# Driver_Stage.net
KiCad netlist of a schematic drawn in Altium Designer
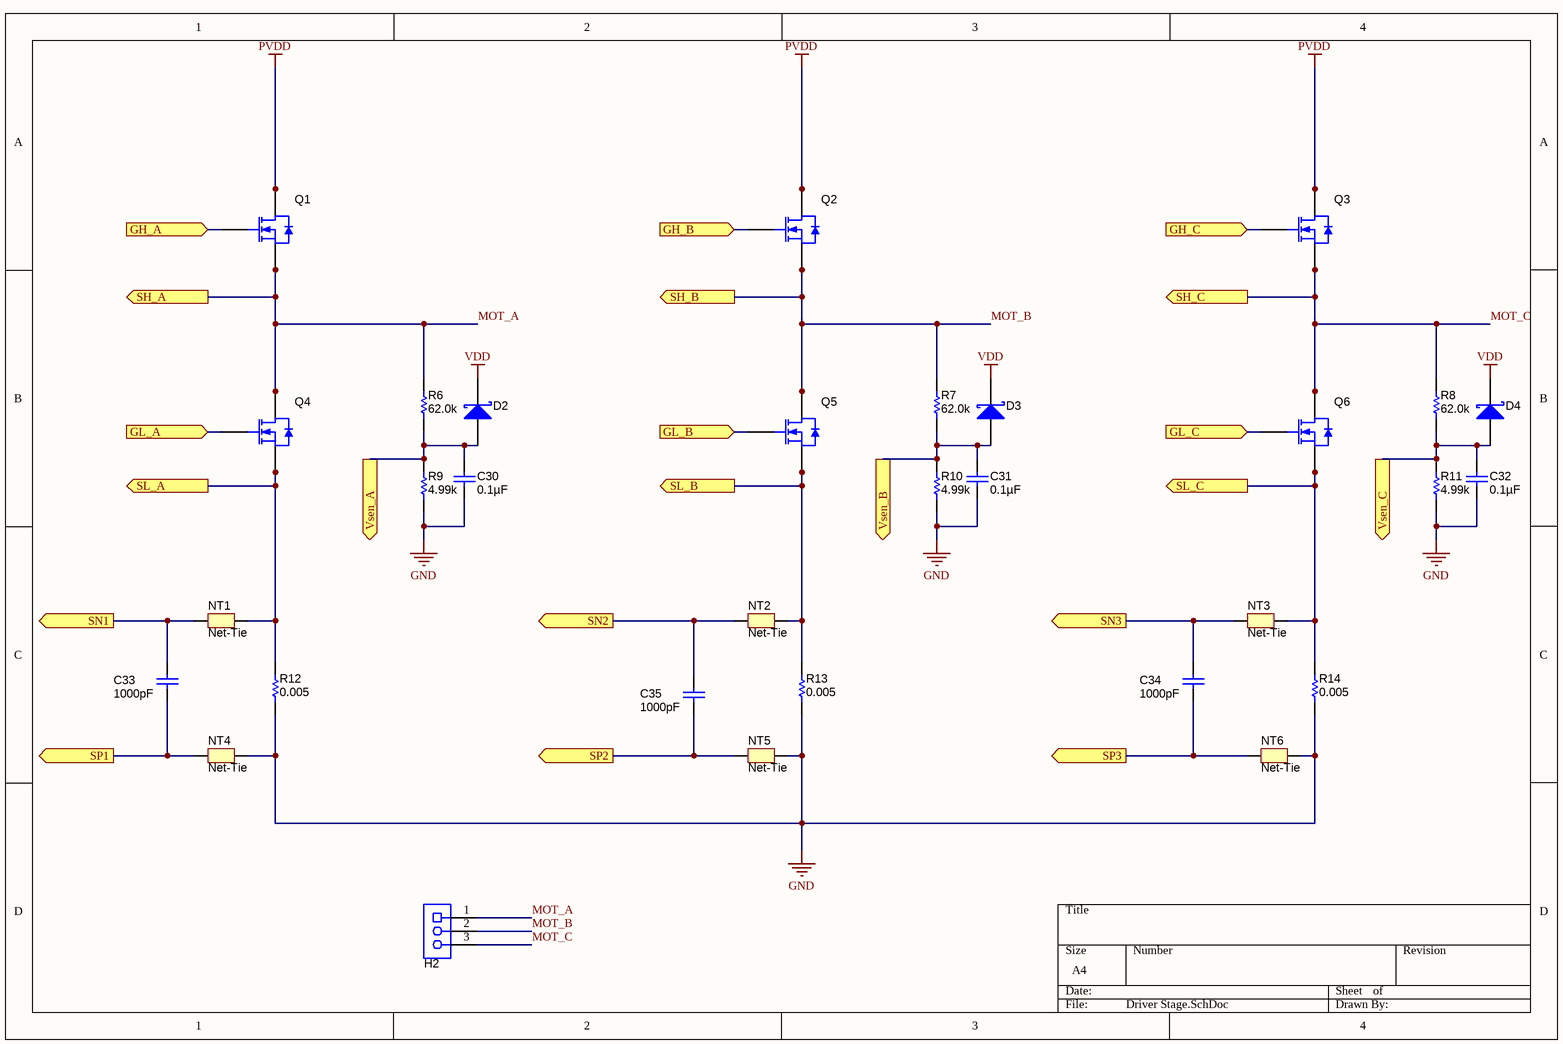
[diagram p0: Driver Stage.SchDoc]

(export (version "E")
  (design (tool "Eeschema 10.0.6"))
  (components
    (comp (ref "C30")
      (value "C0603C104J4RACTU")
      (footprint "MDBU014A:0603L")
      (description "CAP, CERM, 0.1 µF, 16 V, +/- 5%, X7R, 0603")
      (fields
        (field (name "VALUEDISPLAYED") "0.1µF")
        (field (name "MANUFACTURER") "Kemet")
        (field (name "PUBLISHER") "Texas Instruments")
      )
      (libsource (lib "Capacitor_Ceramic") (part "C0603C104J4RACTU"))
    )
    (comp (ref "C31")
      (value "C0603C104J4RACTU")
      (footprint "MDBU014A:0603L")
      (description "CAP, CERM, 0.1 µF, 16 V, +/- 5%, X7R, 0603")
      (fields
        (field (name "VALUEDISPLAYED") "0.1µF")
        (field (name "MANUFACTURER") "Kemet")
        (field (name "PUBLISHER") "Texas Instruments")
      )
      (libsource (lib "Capacitor_Ceramic") (part "C0603C104J4RACTU"))
    )
    (comp (ref "C32")
      (value "C0603C104J4RACTU")
      (footprint "MDBU014A:0603L")
      (description "CAP, CERM, 0.1 µF, 16 V, +/- 5%, X7R, 0603")
      (fields
        (field (name "VALUEDISPLAYED") "0.1µF")
        (field (name "MANUFACTURER") "Kemet")
        (field (name "PUBLISHER") "Texas Instruments")
      )
      (libsource (lib "Capacitor_Ceramic") (part "C0603C104J4RACTU"))
    )
    (comp (ref "C33")
      (value "GRM188R71C102KA01D")
      (footprint "MDBU014A:0603L")
      (description "CAP, CERM, 1000 pF, 16 V, +/- 10%, X7R, 0603")
      (fields
        (field (name "VALUEDISPLAYED") "1000pF")
        (field (name "MANUFACTURER") "MuRata")
        (field (name "PUBLISHER") "Texas Instruments")
      )
      (libsource (lib "Capacitor_Ceramic") (part "GRM188R71C102KA01D"))
    )
    (comp (ref "C34")
      (value "GRM188R71C102KA01D")
      (footprint "MDBU014A:0603L")
      (description "CAP, CERM, 1000 pF, 16 V, +/- 10%, X7R, 0603")
      (fields
        (field (name "VALUEDISPLAYED") "1000pF")
        (field (name "MANUFACTURER") "MuRata")
        (field (name "PUBLISHER") "Texas Instruments")
      )
      (libsource (lib "Capacitor_Ceramic") (part "GRM188R71C102KA01D"))
    )
    (comp (ref "C35")
      (value "GRM188R71C102KA01D")
      (footprint "MDBU014A:0603L")
      (description "CAP, CERM, 1000 pF, 16 V, +/- 10%, X7R, 0603")
      (fields
        (field (name "VALUEDISPLAYED") "1000pF")
        (field (name "MANUFACTURER") "MuRata")
        (field (name "PUBLISHER") "Texas Instruments")
      )
      (libsource (lib "Capacitor_Ceramic") (part "GRM188R71C102KA01D"))
    )
    (comp (ref "D2")
      (value "CD0603-B0130L")
      (footprint "MDBU014A:Diode_0603")
      (description "Diode, Schottky, 35 V, 0.1 A, 0603 Diode")
      (fields (field (name "MANUFACTURER") "Bourns") (field (name "PUBLISHER") "Texas Instruments"))
      (libsource (lib "Diode") (part "CD0603-B0130L"))
    )
    (comp (ref "D3")
      (value "CD0603-B0130L")
      (footprint "MDBU014A:Diode_0603")
      (description "Diode, Schottky, 35 V, 0.1 A, 0603 Diode")
      (fields (field (name "MANUFACTURER") "Bourns") (field (name "PUBLISHER") "Texas Instruments"))
      (libsource (lib "Diode") (part "CD0603-B0130L"))
    )
    (comp (ref "D4")
      (value "CD0603-B0130L")
      (footprint "MDBU014A:Diode_0603")
      (description "Diode, Schottky, 35 V, 0.1 A, 0603 Diode")
      (fields (field (name "MANUFACTURER") "Bourns") (field (name "PUBLISHER") "Texas Instruments"))
      (libsource (lib "Diode") (part "CD0603-B0130L"))
    )
    (comp (ref "H2")
      (value "OSTT7032150")
      (footprint "On-Shore_OSTT7032150")
      (description "Terminal Block, 3x1, 9.52mm, TH")
      (fields
        (field (name "MANUFACTURER") "On-Shore Technology")
        (field (name "SYMBOLCREATOR") "a0412235")
        (field (name "PUBLISHER") "Texas Instruments")
      )
      (libsource (lib "MDBU014A") (part "OSTT7032150"))
    )
    (comp (ref "NT1")
      (value "Net-Tie")
      (footprint "Net-Tie_10mil")
      (description "Single point connection between nets.")
      (fields (field (name "SYMBOLCREATOR") "codlsc") (field (name "PUBLISHER") "Texas Instruments"))
      (libsource (lib "MDBU014A") (part "Net-Tie"))
    )
    (comp (ref "NT2")
      (value "Net-Tie")
      (footprint "Net-Tie_10mil")
      (description "Single point connection between nets.")
      (fields (field (name "SYMBOLCREATOR") "codlsc") (field (name "PUBLISHER") "Texas Instruments"))
      (libsource (lib "MDBU014A") (part "Net-Tie"))
    )
    (comp (ref "NT3")
      (value "Net-Tie")
      (footprint "Net-Tie_10mil")
      (description "Single point connection between nets.")
      (fields (field (name "SYMBOLCREATOR") "codlsc") (field (name "PUBLISHER") "Texas Instruments"))
      (libsource (lib "MDBU014A") (part "Net-Tie"))
    )
    (comp (ref "NT4")
      (value "Net-Tie")
      (footprint "Net-Tie_10mil")
      (description "Single point connection between nets.")
      (fields (field (name "SYMBOLCREATOR") "codlsc") (field (name "PUBLISHER") "Texas Instruments"))
      (libsource (lib "MDBU014A") (part "Net-Tie"))
    )
    (comp (ref "NT5")
      (value "Net-Tie")
      (footprint "Net-Tie_10mil")
      (description "Single point connection between nets.")
      (fields (field (name "SYMBOLCREATOR") "codlsc") (field (name "PUBLISHER") "Texas Instruments"))
      (libsource (lib "MDBU014A") (part "Net-Tie"))
    )
    (comp (ref "NT6")
      (value "Net-Tie")
      (footprint "Net-Tie_10mil")
      (description "Single point connection between nets.")
      (fields (field (name "SYMBOLCREATOR") "codlsc") (field (name "PUBLISHER") "Texas Instruments"))
      (libsource (lib "MDBU014A") (part "Net-Tie"))
    )
    (comp (ref "Q1")
      (value "CSD18540Q5B")
      (footprint "MDBU014A:TRANS_NexFET_Q5B")
      (description "MOSFET, N-CH, 60 V, 28 A, SON 5x6mm")
      (fields
        (field (name "MANUFACTURER") "Texas Instruments")
        (field (name "PUBLISHER") "Texas Instruments")
      )
      (libsource (lib "FETs") (part "CSD18540Q5B"))
    )
    (comp (ref "Q2")
      (value "CSD18540Q5B")
      (footprint "MDBU014A:TRANS_NexFET_Q5B")
      (description "MOSFET, N-CH, 60 V, 28 A, SON 5x6mm")
      (fields
        (field (name "MANUFACTURER") "Texas Instruments")
        (field (name "PUBLISHER") "Texas Instruments")
      )
      (libsource (lib "FETs") (part "CSD18540Q5B"))
    )
    (comp (ref "Q3")
      (value "CSD18540Q5B")
      (footprint "MDBU014A:TRANS_NexFET_Q5B")
      (description "MOSFET, N-CH, 60 V, 28 A, SON 5x6mm")
      (fields
        (field (name "MANUFACTURER") "Texas Instruments")
        (field (name "PUBLISHER") "Texas Instruments")
      )
      (libsource (lib "FETs") (part "CSD18540Q5B"))
    )
    (comp (ref "Q4")
      (value "CSD18540Q5B")
      (footprint "MDBU014A:TRANS_NexFET_Q5B")
      (description "MOSFET, N-CH, 60 V, 28 A, SON 5x6mm")
      (fields
        (field (name "MANUFACTURER") "Texas Instruments")
        (field (name "PUBLISHER") "Texas Instruments")
      )
      (libsource (lib "FETs") (part "CSD18540Q5B"))
    )
    (comp (ref "Q5")
      (value "CSD18540Q5B")
      (footprint "MDBU014A:TRANS_NexFET_Q5B")
      (description "MOSFET, N-CH, 60 V, 28 A, SON 5x6mm")
      (fields
        (field (name "MANUFACTURER") "Texas Instruments")
        (field (name "PUBLISHER") "Texas Instruments")
      )
      (libsource (lib "FETs") (part "CSD18540Q5B"))
    )
    (comp (ref "Q6")
      (value "CSD18540Q5B")
      (footprint "MDBU014A:TRANS_NexFET_Q5B")
      (description "MOSFET, N-CH, 60 V, 28 A, SON 5x6mm")
      (fields
        (field (name "MANUFACTURER") "Texas Instruments")
        (field (name "PUBLISHER") "Texas Instruments")
      )
      (libsource (lib "FETs") (part "CSD18540Q5B"))
    )
    (comp (ref "R6")
      (value "RC0603FR-0762KL")
      (footprint "MDBU014A:0603L")
      (description "RES, 62.0 k, 1%, 0.1 W, 0603")
      (fields
        (field (name "VALUEDISPLAYED") "62.0k")
        (field (name "MANUFACTURER") "Yageo America")
        (field (name "PUBLISHER") "Texas Instruments")
      )
      (libsource (lib "Resistor_0603") (part "RC0603FR-0762KL"))
    )
    (comp (ref "R7")
      (value "RC0603FR-0762KL")
      (footprint "MDBU014A:0603L")
      (description "RES, 62.0 k, 1%, 0.1 W, 0603")
      (fields
        (field (name "VALUEDISPLAYED") "62.0k")
        (field (name "MANUFACTURER") "Yageo America")
        (field (name "PUBLISHER") "Texas Instruments")
      )
      (libsource (lib "Resistor_0603") (part "RC0603FR-0762KL"))
    )
    (comp (ref "R8")
      (value "RC0603FR-0762KL")
      (footprint "MDBU014A:0603L")
      (description "RES, 62.0 k, 1%, 0.1 W, 0603")
      (fields
        (field (name "VALUEDISPLAYED") "62.0k")
        (field (name "MANUFACTURER") "Yageo America")
        (field (name "PUBLISHER") "Texas Instruments")
      )
      (libsource (lib "Resistor_0603") (part "RC0603FR-0762KL"))
    )
    (comp (ref "R9")
      (value "4.99k")
      (footprint "MDBU014A:0603L")
      (description "RES, 4.99 k, 1%, 0.1 W, 0603")
      (fields
        (field (name "PARTNUMBER") "CRCW06034K99FKEA")
        (field (name "MANUFACTURER") "Vishay-Dale")
        (field (name "PUBLISHER") "Texas Instruments")
      )
      (libsource (lib "Resistor_0603") (part "CRCW06034K99FKEA"))
    )
    (comp (ref "R10")
      (value "4.99k")
      (footprint "MDBU014A:0603L")
      (description "RES, 4.99 k, 1%, 0.1 W, 0603")
      (fields
        (field (name "PARTNUMBER") "CRCW06034K99FKEA")
        (field (name "MANUFACTURER") "Vishay-Dale")
        (field (name "PUBLISHER") "Texas Instruments")
      )
      (libsource (lib "Resistor_0603") (part "CRCW06034K99FKEA"))
    )
    (comp (ref "R11")
      (value "4.99k")
      (footprint "MDBU014A:0603L")
      (description "RES, 4.99 k, 1%, 0.1 W, 0603")
      (fields
        (field (name "PARTNUMBER") "CRCW06034K99FKEA")
        (field (name "MANUFACTURER") "Vishay-Dale")
        (field (name "PUBLISHER") "Texas Instruments")
      )
      (libsource (lib "Resistor_0603") (part "CRCW06034K99FKEA"))
    )
    (comp (ref "R12")
      (value "LRMAP2512-R005FT4")
      (footprint "MDBU014A:2512")
      (description "RES SMD 0.005 OHM 1% 3W 2512")
      (fields
        (field (name "VALUEDISPLAYED") "0.005")
        (field (name "MANUFACTURER") "TT Electronics/Welwyn")
        (field (name "PUBLISHER") "Texas Instruments")
      )
      (libsource (lib "Resistor_2512") (part "PMR100HZPFU5L00"))
    )
    (comp (ref "R13")
      (value "LRMAP2512-R005FT4")
      (footprint "MDBU014A:2512")
      (description "RES SMD 0.005 OHM 1% 3W 2512")
      (fields
        (field (name "VALUEDISPLAYED") "0.005")
        (field (name "MANUFACTURER") "TT Electronics/Welwyn")
        (field (name "PUBLISHER") "Texas Instruments")
      )
      (libsource (lib "Resistor_2512") (part "PMR100HZPFU5L00"))
    )
    (comp (ref "R14")
      (value "LRMAP2512-R005FT4")
      (footprint "MDBU014A:2512")
      (description "RES SMD 0.005 OHM 1% 3W 2512")
      (fields
        (field (name "VALUEDISPLAYED") "0.005")
        (field (name "MANUFACTURER") "TT Electronics/Welwyn")
        (field (name "PUBLISHER") "Texas Instruments")
      )
      (libsource (lib "Resistor_2512") (part "PMR100HZPFU5L00"))
    )
  )
  (nets
    (net (code "1") (name "/GH_A") (class "Default")
      (node (ref "Q1") (pin "4") (pinfunction "G_4") (pintype "passive"))
    )
    (net (code "2") (name "/GH_B") (class "Default")
      (node (ref "Q2") (pin "4") (pinfunction "G_4") (pintype "passive"))
    )
    (net (code "3") (name "/GH_C") (class "Default")
      (node (ref "Q3") (pin "4") (pinfunction "G_4") (pintype "passive"))
    )
    (net (code "4") (name "/GL_A") (class "Default")
      (node (ref "Q4") (pin "4") (pinfunction "G_4") (pintype "passive"))
    )
    (net (code "5") (name "/GL_B") (class "Default")
      (node (ref "Q5") (pin "4") (pinfunction "G_4") (pintype "passive"))
    )
    (net (code "6") (name "/GL_C") (class "Default")
      (node (ref "Q6") (pin "4") (pinfunction "G_4") (pintype "passive"))
    )
    (net (code "7") (name "/MOT_A") (class "Default")
      (node (ref "H2") (pin "1") (pinfunction "1_1") (pintype "passive"))
      (node (ref "Q1") (pin "1") (pinfunction "S_1") (pintype "passive"))
      (node (ref "Q1") (pin "2") (pinfunction "S_2") (pintype "passive"))
      (node (ref "Q1") (pin "3") (pinfunction "S_3") (pintype "passive"))
      (node (ref "Q4") (pin "5") (pinfunction "D_5") (pintype "passive"))
      (node (ref "Q4") (pin "6") (pinfunction "D_6") (pintype "passive"))
      (node (ref "Q4") (pin "7") (pinfunction "D_7") (pintype "passive"))
      (node (ref "Q4") (pin "8") (pinfunction "D_8") (pintype "passive"))
      (node (ref "R6") (pin "2") (pinfunction "2_2") (pintype "passive"))
    )
    (net (code "8") (name "/MOT_B") (class "Default")
      (node (ref "H2") (pin "2") (pinfunction "2_2") (pintype "passive"))
      (node (ref "Q2") (pin "1") (pinfunction "S_1") (pintype "passive"))
      (node (ref "Q2") (pin "2") (pinfunction "S_2") (pintype "passive"))
      (node (ref "Q2") (pin "3") (pinfunction "S_3") (pintype "passive"))
      (node (ref "Q5") (pin "5") (pinfunction "D_5") (pintype "passive"))
      (node (ref "Q5") (pin "6") (pinfunction "D_6") (pintype "passive"))
      (node (ref "Q5") (pin "7") (pinfunction "D_7") (pintype "passive"))
      (node (ref "Q5") (pin "8") (pinfunction "D_8") (pintype "passive"))
      (node (ref "R7") (pin "2") (pinfunction "2_2") (pintype "passive"))
    )
    (net (code "9") (name "/MOT_C") (class "Default")
      (node (ref "H2") (pin "3") (pinfunction "3_3") (pintype "passive"))
      (node (ref "Q3") (pin "1") (pinfunction "S_1") (pintype "passive"))
      (node (ref "Q3") (pin "2") (pinfunction "S_2") (pintype "passive"))
      (node (ref "Q3") (pin "3") (pinfunction "S_3") (pintype "passive"))
      (node (ref "Q6") (pin "5") (pinfunction "D_5") (pintype "passive"))
      (node (ref "Q6") (pin "6") (pinfunction "D_6") (pintype "passive"))
      (node (ref "Q6") (pin "7") (pinfunction "D_7") (pintype "passive"))
      (node (ref "Q6") (pin "8") (pinfunction "D_8") (pintype "passive"))
      (node (ref "R8") (pin "2") (pinfunction "2_2") (pintype "passive"))
    )
    (net (code "10") (name "/SL_A") (class "Default")
      (node (ref "NT1") (pin "2") (pinfunction "2_2") (pintype "passive"))
      (node (ref "Q4") (pin "1") (pinfunction "S_1") (pintype "passive"))
      (node (ref "Q4") (pin "2") (pinfunction "S_2") (pintype "passive"))
      (node (ref "Q4") (pin "3") (pinfunction "S_3") (pintype "passive"))
      (node (ref "R12") (pin "2") (pinfunction "2_2") (pintype "passive"))
    )
    (net (code "11") (name "/SL_B") (class "Default")
      (node (ref "NT2") (pin "2") (pinfunction "2_2") (pintype "passive"))
      (node (ref "Q5") (pin "1") (pinfunction "S_1") (pintype "passive"))
      (node (ref "Q5") (pin "2") (pinfunction "S_2") (pintype "passive"))
      (node (ref "Q5") (pin "3") (pinfunction "S_3") (pintype "passive"))
      (node (ref "R13") (pin "2") (pinfunction "2_2") (pintype "passive"))
    )
    (net (code "12") (name "/SL_C") (class "Default")
      (node (ref "NT3") (pin "2") (pinfunction "2_2") (pintype "passive"))
      (node (ref "Q6") (pin "1") (pinfunction "S_1") (pintype "passive"))
      (node (ref "Q6") (pin "2") (pinfunction "S_2") (pintype "passive"))
      (node (ref "Q6") (pin "3") (pinfunction "S_3") (pintype "passive"))
      (node (ref "R14") (pin "2") (pinfunction "2_2") (pintype "passive"))
    )
    (net (code "13") (name "/SN1") (class "Default")
      (node (ref "C33") (pin "1") (pinfunction "1_1") (pintype "passive"))
      (node (ref "NT1") (pin "1") (pinfunction "1_1") (pintype "passive"))
    )
    (net (code "14") (name "/SN2") (class "Default")
      (node (ref "C35") (pin "1") (pinfunction "1_1") (pintype "passive"))
      (node (ref "NT2") (pin "1") (pinfunction "1_1") (pintype "passive"))
    )
    (net (code "15") (name "/SN3") (class "Default")
      (node (ref "C34") (pin "1") (pinfunction "1_1") (pintype "passive"))
      (node (ref "NT3") (pin "1") (pinfunction "1_1") (pintype "passive"))
    )
    (net (code "16") (name "/SP1") (class "Default")
      (node (ref "C33") (pin "2") (pinfunction "2_2") (pintype "passive"))
      (node (ref "NT4") (pin "1") (pinfunction "1_1") (pintype "passive"))
    )
    (net (code "17") (name "/SP2") (class "Default")
      (node (ref "C35") (pin "2") (pinfunction "2_2") (pintype "passive"))
      (node (ref "NT5") (pin "1") (pinfunction "1_1") (pintype "passive"))
    )
    (net (code "18") (name "/SP3") (class "Default")
      (node (ref "C34") (pin "2") (pinfunction "2_2") (pintype "passive"))
      (node (ref "NT6") (pin "1") (pinfunction "1_1") (pintype "passive"))
    )
    (net (code "19") (name "/Vsen_A") (class "Default")
      (node (ref "C30") (pin "1") (pinfunction "1_1") (pintype "passive"))
      (node (ref "D2") (pin "2") (pinfunction "A_2") (pintype "passive"))
      (node (ref "R6") (pin "1") (pinfunction "1_1") (pintype "passive"))
      (node (ref "R9") (pin "2") (pinfunction "2_2") (pintype "passive"))
    )
    (net (code "20") (name "/Vsen_B") (class "Default")
      (node (ref "C31") (pin "1") (pinfunction "1_1") (pintype "passive"))
      (node (ref "D3") (pin "2") (pinfunction "A_2") (pintype "passive"))
      (node (ref "R10") (pin "2") (pinfunction "2_2") (pintype "passive"))
      (node (ref "R7") (pin "1") (pinfunction "1_1") (pintype "passive"))
    )
    (net (code "21") (name "/Vsen_C") (class "Default")
      (node (ref "C32") (pin "1") (pinfunction "1_1") (pintype "passive"))
      (node (ref "D4") (pin "2") (pinfunction "A_2") (pintype "passive"))
      (node (ref "R11") (pin "2") (pinfunction "2_2") (pintype "passive"))
      (node (ref "R8") (pin "1") (pinfunction "1_1") (pintype "passive"))
    )
    (net (code "22") (name "GND") (class "Default")
      (node (ref "C30") (pin "2") (pinfunction "2_2") (pintype "passive"))
      (node (ref "C31") (pin "2") (pinfunction "2_2") (pintype "passive"))
      (node (ref "C32") (pin "2") (pinfunction "2_2") (pintype "passive"))
      (node (ref "NT4") (pin "2") (pinfunction "2_2") (pintype "passive"))
      (node (ref "NT5") (pin "2") (pinfunction "2_2") (pintype "passive"))
      (node (ref "NT6") (pin "2") (pinfunction "2_2") (pintype "passive"))
      (node (ref "R10") (pin "1") (pinfunction "1_1") (pintype "passive"))
      (node (ref "R11") (pin "1") (pinfunction "1_1") (pintype "passive"))
      (node (ref "R12") (pin "1") (pinfunction "1_1") (pintype "passive"))
      (node (ref "R13") (pin "1") (pinfunction "1_1") (pintype "passive"))
      (node (ref "R14") (pin "1") (pinfunction "1_1") (pintype "passive"))
      (node (ref "R9") (pin "1") (pinfunction "1_1") (pintype "passive"))
    )
    (net (code "23") (name "PVDD") (class "Default")
      (node (ref "Q1") (pin "5") (pinfunction "D_5") (pintype "passive"))
      (node (ref "Q1") (pin "6") (pinfunction "D_6") (pintype "passive"))
      (node (ref "Q1") (pin "7") (pinfunction "D_7") (pintype "passive"))
      (node (ref "Q1") (pin "8") (pinfunction "D_8") (pintype "passive"))
      (node (ref "Q2") (pin "5") (pinfunction "D_5") (pintype "passive"))
      (node (ref "Q2") (pin "6") (pinfunction "D_6") (pintype "passive"))
      (node (ref "Q2") (pin "7") (pinfunction "D_7") (pintype "passive"))
      (node (ref "Q2") (pin "8") (pinfunction "D_8") (pintype "passive"))
      (node (ref "Q3") (pin "5") (pinfunction "D_5") (pintype "passive"))
      (node (ref "Q3") (pin "6") (pinfunction "D_6") (pintype "passive"))
      (node (ref "Q3") (pin "7") (pinfunction "D_7") (pintype "passive"))
      (node (ref "Q3") (pin "8") (pinfunction "D_8") (pintype "passive"))
    )
    (net (code "24") (name "VDD") (class "Default")
      (node (ref "D2") (pin "1") (pinfunction "K_1") (pintype "passive"))
      (node (ref "D3") (pin "1") (pinfunction "K_1") (pintype "passive"))
      (node (ref "D4") (pin "1") (pinfunction "K_1") (pintype "passive"))
    )
  )
)
